# 13_-_I2C_EEPROM.net
KiCad netlist of a schematic drawn in Altium Designer
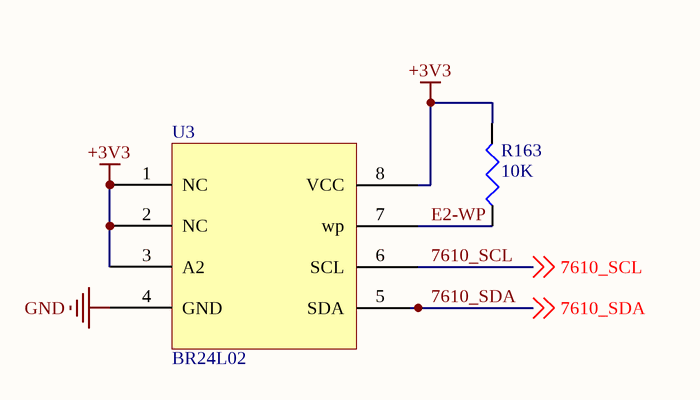
[diagram p0: [13] - I2C_EEPROM.SchDoc]

(export (version "E")
  (design (tool "Eeschema 10.0.6"))
  (components
    (comp (ref "R163")
      (value "10K")
      (footprint "R0402")
      (description "RES 1.00 OHM 1/16W 1% 0402 SM")
      (fields
        (field (name "MANUFACTURER") "Yageo")
        (field (name "MANUFACTURER PART NUMBER") "RC0402FR-071RL")
      )
      (libsource (lib "Integrated_Library_RF_FEB_2012") (part "RC0402FR-071RL"))
    )
    (comp (ref "U3") (value "BR24L02") (footprint "SO-8") (libsource (lib "XYUSB1") (part "24C08AN")))
  )
  (nets
    (net (code "1") (name "+3V3") (class "Default")
      (node (ref "R163") (pin "2") (pinfunction "2_2") (pintype "passive"))
      (node (ref "U3") (pin "1") (pinfunction "NC_1") (pintype "passive"))
      (node (ref "U3") (pin "2") (pinfunction "NC_2") (pintype "passive"))
      (node (ref "U3") (pin "3") (pinfunction "A2_3") (pintype "passive"))
      (node (ref "U3") (pin "8") (pinfunction "VCC_8") (pintype "passive"))
    )
    (net (code "2") (name "/E2-WP") (class "Default")
      (node (ref "R163") (pin "1") (pinfunction "1_1") (pintype "passive"))
      (node (ref "U3") (pin "7") (pinfunction "wp_7") (pintype "passive"))
    )
    (net (code "3") (name "7610_SCL") (class "Default")
      (node (ref "U3") (pin "6") (pinfunction "SCL_6") (pintype "passive"))
    )
    (net (code "4") (name "7610_SDA") (class "Default")
      (node (ref "U3") (pin "5") (pinfunction "SDA_5") (pintype "passive"))
    )
    (net (code "5") (name "GND") (class "Default")
      (node (ref "U3") (pin "4") (pinfunction "GND_4") (pintype "passive"))
    )
  )
)
